# Power_Tree.net
KiCad netlist of a schematic drawn in Altium Designer
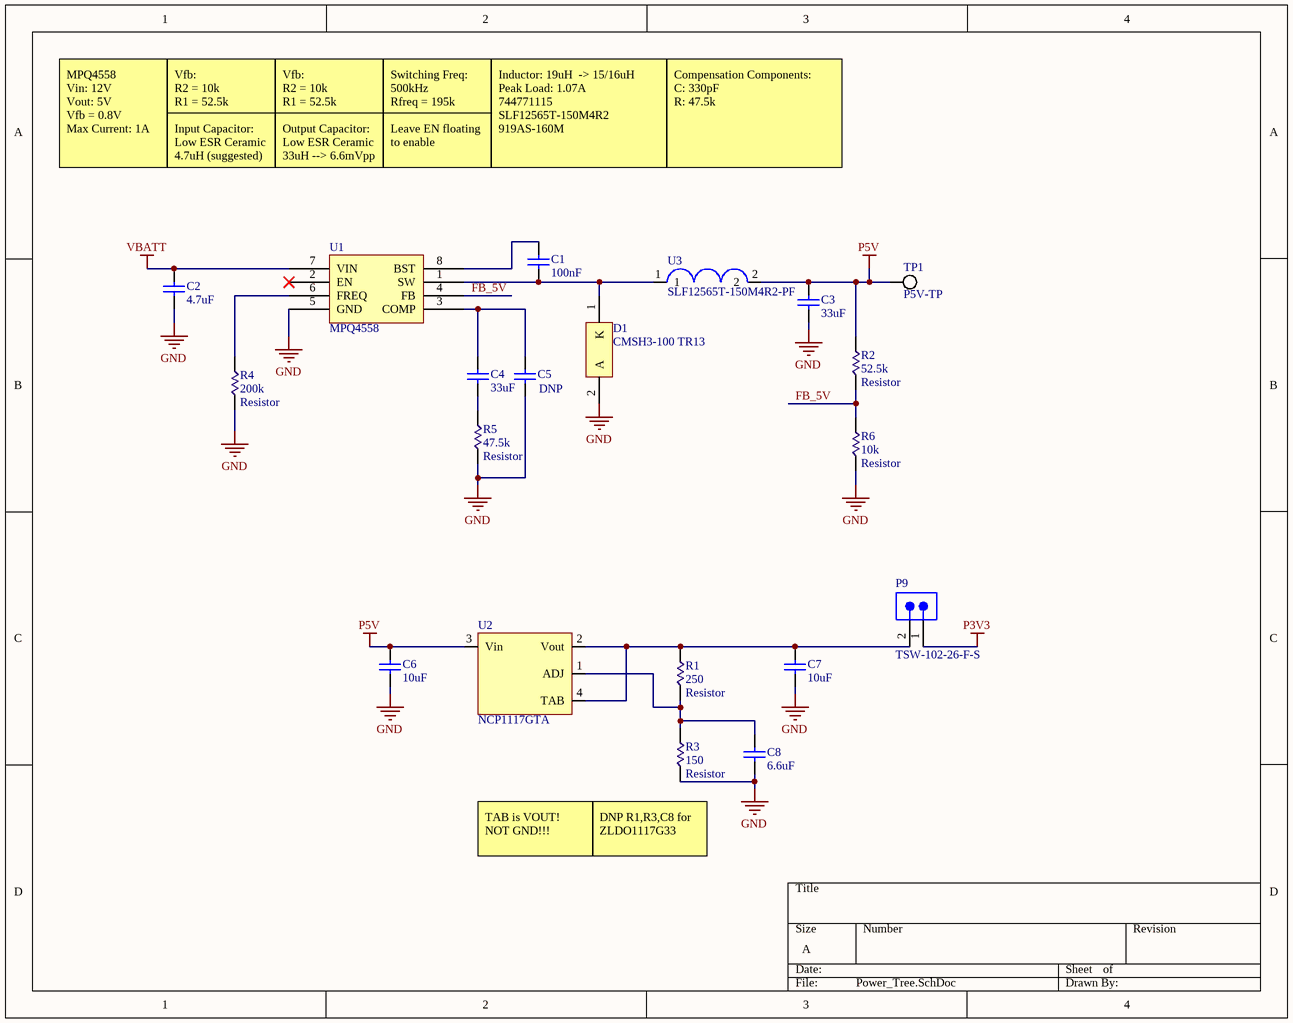
[diagram p0: Power_Tree.SchDoc]

(export (version "E")
  (design (tool "Eeschema 10.0.6"))
  (components
    (comp (ref "C1")
      (value "100nF")
      (footprint "FOOTPRINT-1206-GEN")
      (description "CAP CER 100nF 50V X7R 1206 ±10% 50V Ceramic Capacitor X7R 1206 (3216 Metric)")
      (fields
        (field (name "PART NUMBER") "1276-6781-1-ND")
        (field (name "Comment") "100nF 1206")
        (field (name "PUBLISHER") "Altium Limited")
      )
      (libsource (lib "") (part "Symbol_1"))
    )
    (comp (ref "C2")
      (value "4.7uF")
      (footprint "FOOTPRINT-1206-GEN")
      (description "CAP CER 4.7UF 50V X7R 1206 ±10% 50V Ceramic Capacitor X7R 1206 (3216 Metric)")
      (fields
        (field (name "PART NUMBER") "1276-6781-1-ND")
        (field (name "Comment") "CL31B475KBHVPNE")
        (field (name "PUBLISHER") "Altium Limited")
      )
      (libsource (lib "") (part "Symbol_1"))
    )
    (comp (ref "C3")
      (value "33uF")
      (footprint "FOOTPRINT-1206-GEN")
      (description "CAP CER 33UF 50V X7R 1206 ±10% 50V Ceramic Capacitor X7R 1206 (3216 Metric)")
      (fields (field (name "PART NUMBER") "1276-6781-1-ND") (field (name "PUBLISHER") "Altium Limited"))
      (libsource (lib "") (part "Symbol_1"))
    )
    (comp (ref "C4")
      (value "33uF")
      (footprint "FOOTPRINT-1206-GEN")
      (description "CAP CER 33UF 50V X7R 1206 ±10% 50V Ceramic Capacitor X7R 1206 (3216 Metric)")
      (fields (field (name "PART NUMBER") "1276-6781-1-ND") (field (name "PUBLISHER") "Altium Limited"))
      (libsource (lib "") (part "Symbol_1"))
    )
    (comp (ref "C5")
      (value "DNP")
      (footprint "FOOTPRINT-1206-GEN")
      (description "1206")
      (fields (field (name "PART NUMBER") "1276-6781-1-ND") (field (name "PUBLISHER") "Altium Limited"))
      (libsource (lib "") (part "Symbol_1"))
    )
    (comp (ref "C6")
      (value "10uF")
      (footprint "FOOTPRINT-1206-GEN")
      (description "CAP CER 10UF 50V X7R 1206 ±10% 50V Ceramic Capacitor X7R 1206 (3216 Metric)")
      (fields (field (name "PART NUMBER") "1276-6781-1-ND") (field (name "PUBLISHER") "Altium Limited"))
      (libsource (lib "") (part "Symbol_1"))
    )
    (comp (ref "C7")
      (value "10uF")
      (footprint "FOOTPRINT-1206-GEN")
      (description "CAP CER 10UF 50V X7R 1206 ±10% 50V Ceramic Capacitor X7R 1206 (3216 Metric)")
      (fields (field (name "PART NUMBER") "1276-6781-1-ND") (field (name "PUBLISHER") "Altium Limited"))
      (libsource (lib "") (part "Symbol_1"))
    )
    (comp (ref "C8")
      (value "6.6uF")
      (footprint "FOOTPRINT-1206-GEN")
      (description "CAP CER 6.6UF 50V X7R 1206 ±10% 50V Ceramic Capacitor X7R 1206 (3216 Metric)")
      (fields (field (name "PART NUMBER") "1276-6781-1-ND") (field (name "PUBLISHER") "Altium Limited"))
      (libsource (lib "") (part "Symbol_1"))
    )
    (comp (ref "D1")
      (value "CMSH3-100 TR13")
      (footprint "ONSC-SMB-2-403A-03_V")
      (description "CMSH3-100 TR13 Schottky Power Rectifier, 2-Pin SMB, Pb-Free, Tape and Reel")
      (fields (field (name "PARTNUMBER") "SS22T3G") (field (name "MANUFACTURER") "On Semiconductor"))
      (libsource (lib "Altium Content Vault") (part "ONSC-D-K1A2-2_A"))
    )
    (comp (ref "P9")
      (value "TSW-102-26-F-S")
      (footprint "SMTC-TSW-102-26-XX-S")
      (description "Headers & Wire Housings Classic PCB Header Strips, 0.100 pitch")
      (libsource (lib "University of California Riverside - FSAE") (part "SMTC-TSW-102-X-X-S-X"))
    )
    (comp (ref "R1")
      (value "250")
      (footprint "FOOTPRINT-1206-GEN")
      (description "250 ±1% 0.25W, 1/4W Chip Resistor 1206 (3216 Metric) Automotive AEC-Q200 Thick Film")
      (fields (field (name "TYPE") "Resistor") (field (name "Comment") "Resistor 250 +/-1% 1206 1/4W"))
      (libsource (lib "University of California Riverside - FSAE") (part "Symbol"))
    )
    (comp (ref "R2")
      (value "52.5k")
      (footprint "FOOTPRINT-1206-GEN")
      (description "52.5k ±1% 0.25W, 1/4W Chip Resistor 1206 (3216 Metric) Automotive AEC-Q200 Thick Film")
      (fields (field (name "TYPE") "Resistor") (field (name "Comment") "Resistor 52.5k +/-1% 1206 1/4W"))
      (libsource (lib "University of California Riverside - FSAE") (part "Symbol"))
    )
    (comp (ref "R3")
      (value "150")
      (footprint "FOOTPRINT-1206-GEN")
      (description "150 ±1% 0.25W, 1/4W Chip Resistor 1206 (3216 Metric) Automotive AEC-Q200 Thick Film")
      (fields (field (name "TYPE") "Resistor") (field (name "Comment") "Resistor 150 +/-1% 1206 1/4W"))
      (libsource (lib "University of California Riverside - FSAE") (part "Symbol"))
    )
    (comp (ref "R4")
      (value "200k")
      (footprint "FOOTPRINT-1206-GEN")
      (description "200k ±1% 0.25W, 1/4W Chip Resistor 1206 (3216 Metric) Automotive AEC-Q200 Thick Film")
      (fields (field (name "TYPE") "Resistor") (field (name "Comment") "Resistor 200k +/-1% 1206 1/4W"))
      (libsource (lib "University of California Riverside - FSAE") (part "Symbol"))
    )
    (comp (ref "R5")
      (value "47.5k")
      (footprint "FOOTPRINT-1206-GEN")
      (description "47.5k ±1% 0.25W, 1/4W Chip Resistor 1206 (3216 Metric) Automotive AEC-Q200 Thick Film")
      (fields (field (name "TYPE") "Resistor") (field (name "Comment") "Resistor 47.5k +/-1% 1206 1/4W"))
      (libsource (lib "University of California Riverside - FSAE") (part "Symbol"))
    )
    (comp (ref "R6")
      (value "10k")
      (footprint "FOOTPRINT-1206-GEN")
      (description "10k ±1% 0.25W, 1/4W Chip Resistor 1206 (3216 Metric) Automotive AEC-Q200 Thick Film")
      (fields (field (name "TYPE") "Resistor") (field (name "Comment") "Resistor 10k +/-1% 1206 1/4W"))
      (libsource (lib "University of California Riverside - FSAE") (part "Symbol"))
    )
    (comp (ref "TP1")
      (value "P5V-TP")
      (footprint "FOOTPRINT-GENERIC-TP-VIA-1MM")
      (libsource (lib "University of California Riverside - FSAE") (part "Misc-Generic-TP"))
    )
    (comp (ref "U1")
      (value "MPQ4558")
      (footprint "SOIC127P601X173-9N")
      (libsource (lib "University of California Riverside - FSAE") (part "MPQ4558"))
    )
    (comp (ref "U2")
      (value "NCP1117GTA")
      (footprint "SOT230P700X180-4N")
      (libsource (lib "Schlib1") (part "NCP1117GTA"))
    )
    (comp (ref "U3")
      (value "SLF12565T-150M4R2-PF")
      (footprint "0.492\" x 0.492\"")
      (libsource (lib "Schlib1") (part "SLF12565T-150M4R2-PF"))
    )
  )
  (nets
    (net (code "1") (name "/FB_5V") (class "Default")
      (node (ref "R2") (pin "1") (pinfunction "1_1") (pintype "passive"))
      (node (ref "R6") (pin "2") (pinfunction "2_2") (pintype "passive"))
      (node (ref "U1") (pin "4") (pinfunction "FB_4") (pintype "passive"))
    )
    (net (code "2") (name "GND") (class "Default")
      (node (ref "C2") (pin "1") (pinfunction "1_1") (pintype "passive"))
      (node (ref "C3") (pin "1") (pinfunction "1_1") (pintype "passive"))
      (node (ref "C5") (pin "1") (pinfunction "1_1") (pintype "passive"))
      (node (ref "C6") (pin "1") (pinfunction "1_1") (pintype "passive"))
      (node (ref "C7") (pin "1") (pinfunction "1_1") (pintype "passive"))
      (node (ref "C8") (pin "1") (pinfunction "1_1") (pintype "passive"))
      (node (ref "D1") (pin "2") (pinfunction "A_2") (pintype "passive"))
      (node (ref "R3") (pin "1") (pinfunction "1_1") (pintype "passive"))
      (node (ref "R4") (pin "1") (pinfunction "1_1") (pintype "passive"))
      (node (ref "R5") (pin "1") (pinfunction "1_1") (pintype "passive"))
      (node (ref "R6") (pin "1") (pinfunction "1_1") (pintype "passive"))
      (node (ref "U1") (pin "5") (pinfunction "GND_5") (pintype "passive"))
    )
    (net (code "3") (name "Net-(C4-Pad1)") (class "Default")
      (node (ref "C4") (pin "1") (pinfunction "1_1") (pintype "passive"))
      (node (ref "R5") (pin "2") (pinfunction "2_2") (pintype "passive"))
    )
    (net (code "4") (name "Net-(D1-K)") (class "Default")
      (node (ref "C1") (pin "1") (pinfunction "1_1") (pintype "passive"))
      (node (ref "D1") (pin "1") (pinfunction "K_1") (pintype "passive"))
      (node (ref "U1") (pin "1") (pinfunction "SW_1") (pintype "passive"))
      (node (ref "U3") (pin "1") (pinfunction "1_1") (pintype "passive"))
    )
    (net (code "5") (name "Net-(U1-BST)") (class "Default")
      (node (ref "C1") (pin "2") (pinfunction "2_2") (pintype "passive"))
      (node (ref "U1") (pin "8") (pinfunction "BST_8") (pintype "passive"))
    )
    (net (code "6") (name "Net-(U1-COMP)") (class "Default")
      (node (ref "C4") (pin "2") (pinfunction "2_2") (pintype "passive"))
      (node (ref "C5") (pin "2") (pinfunction "2_2") (pintype "passive"))
      (node (ref "U1") (pin "3") (pinfunction "COMP_3") (pintype "passive"))
    )
    (net (code "7") (name "Net-(U1-FREQ)") (class "Default")
      (node (ref "R4") (pin "2") (pinfunction "2_2") (pintype "passive"))
      (node (ref "U1") (pin "6") (pinfunction "FREQ_6") (pintype "passive"))
    )
    (net (code "8") (name "Net-(U2-ADJ)") (class "Default")
      (node (ref "C8") (pin "2") (pinfunction "2_2") (pintype "passive"))
      (node (ref "R1") (pin "1") (pinfunction "1_1") (pintype "passive"))
      (node (ref "R3") (pin "2") (pinfunction "2_2") (pintype "passive"))
      (node (ref "U2") (pin "1") (pinfunction "ADJ_1") (pintype "passive"))
    )
    (net (code "9") (name "Net-(U2-TAB)") (class "Default")
      (node (ref "C7") (pin "2") (pinfunction "2_2") (pintype "passive"))
      (node (ref "P9") (pin "2") (pinfunction "2_2") (pintype "passive"))
      (node (ref "R1") (pin "2") (pinfunction "2_2") (pintype "passive"))
      (node (ref "U2") (pin "2") (pinfunction "Vout_2") (pintype "passive"))
      (node (ref "U2") (pin "4") (pinfunction "TAB_4") (pintype "passive"))
    )
    (net (code "10") (name "P3V3") (class "Default")
      (node (ref "P9") (pin "1") (pinfunction "1_1") (pintype "passive"))
    )
    (net (code "11") (name "P5V") (class "Default")
      (node (ref "C3") (pin "2") (pinfunction "2_2") (pintype "passive"))
      (node (ref "C6") (pin "2") (pinfunction "2_2") (pintype "passive"))
      (node (ref "R2") (pin "2") (pinfunction "2_2") (pintype "passive"))
      (node (ref "TP1") (pin "1") (pinfunction "TP_1") (pintype "passive"))
      (node (ref "U2") (pin "3") (pinfunction "Vin_3") (pintype "passive"))
      (node (ref "U3") (pin "2") (pinfunction "2_2") (pintype "passive"))
    )
    (net (code "12") (name "VBATT") (class "Default")
      (node (ref "C2") (pin "2") (pinfunction "2_2") (pintype "passive"))
      (node (ref "U1") (pin "7") (pinfunction "VIN_7") (pintype "passive"))
    )
    (net (code "13") (name "unconnected-(U1-EN-Pad2)") (class "Default")
      (node (ref "U1") (pin "2") (pinfunction "EN_2") (pintype "passive+no_connect"))
    )
  )
)
